# 25LC020A.net
KiCad netlist of a schematic drawn in EAGLE
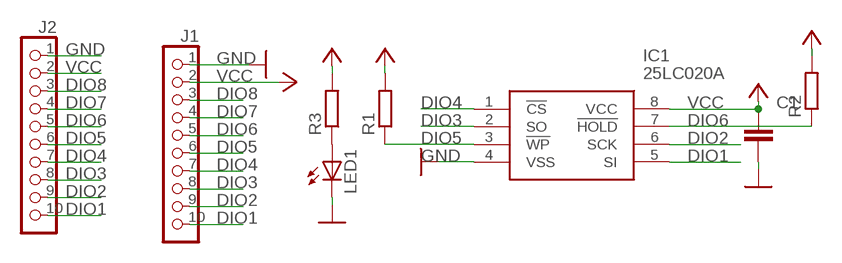
[diagram p0: schematic, sheet 1]

(export (version "E")
  (design (tool "Eeschema 10.0.6"))
  (components
    (comp (ref "C1")
      (value "CAPACITOR_NPOL-0603")
      (footprint "eagle-import:C603")
      (libsource (lib "eagle-import") (part "CAPACITOR_NPOL-0603"))
    )
    (comp (ref "IC1")
      (value "25LC020A")
      (footprint "eagle-import:SOIC127P600X175-8N")
      (fields (field (name "MANUFACTURER_PART_NUMBER") "25LC020A-I/SN"))
      (libsource (lib "eagle-import") (part "25LC020A-I_SN"))
    )
    (comp (ref "J1")
      (value "CON_HEADER_1X10-RIGHT_ANGLED_PTH")
      (footprint "eagle-import:M1X10_FEMALE_RIGHT_ANGLED_PTH")
      (libsource (lib "eagle-import") (part "CON_HEADER_1X10-RIGHT_ANGLED_PTH"))
    )
    (comp (ref "J2")
      (value "CON_HEADER_1X10-PTH")
      (footprint "eagle-import:M1X10")
      (libsource (lib "eagle-import") (part "CON_HEADER_1X10-PTH"))
    )
    (comp (ref "LED1")
      (value "LED-0805")
      (footprint "eagle-import:LED-805")
      (libsource (lib "eagle-import") (part "LED-0805"))
    )
    (comp (ref "R1")
      (value "RESISTOR-0603")
      (footprint "eagle-import:R603")
      (libsource (lib "eagle-import") (part "RESISTOR-0603"))
    )
    (comp (ref "R2")
      (value "RESISTOR-0603")
      (footprint "eagle-import:R603")
      (libsource (lib "eagle-import") (part "RESISTOR-0603"))
    )
    (comp (ref "R3")
      (value "RESISTOR-0603")
      (footprint "eagle-import:R603")
      (libsource (lib "eagle-import") (part "RESISTOR-0603"))
    )
  )
  (nets
    (net (code "1") (name "/DIO1") (class "Default")
      (node (ref "IC1") (pin "5") (pinfunction "SI_5") (pintype "bidirectional"))
      (node (ref "J1") (pin "10") (pinfunction "10_10") (pintype "passive"))
      (node (ref "J2") (pin "10") (pinfunction "10_10") (pintype "passive"))
    )
    (net (code "2") (name "/DIO2") (class "Default")
      (node (ref "IC1") (pin "6") (pinfunction "SCK_6") (pintype "bidirectional"))
      (node (ref "J1") (pin "9") (pinfunction "9_9") (pintype "passive"))
      (node (ref "J2") (pin "9") (pinfunction "9_9") (pintype "passive"))
    )
    (net (code "3") (name "/DIO3") (class "Default")
      (node (ref "IC1") (pin "2") (pinfunction "SO_2") (pintype "bidirectional"))
      (node (ref "J1") (pin "8") (pinfunction "8_8") (pintype "passive"))
      (node (ref "J2") (pin "8") (pinfunction "8_8") (pintype "passive"))
    )
    (net (code "4") (name "/DIO4") (class "Default")
      (node (ref "IC1") (pin "1") (pinfunction "~{CS}_1") (pintype "input"))
      (node (ref "J1") (pin "7") (pinfunction "7_7") (pintype "passive"))
      (node (ref "J2") (pin "7") (pinfunction "7_7") (pintype "passive"))
    )
    (net (code "5") (name "/DIO5") (class "Default")
      (node (ref "IC1") (pin "3") (pinfunction "~{WP}_3") (pintype "bidirectional"))
      (node (ref "J1") (pin "6") (pinfunction "6_6") (pintype "passive"))
      (node (ref "J2") (pin "6") (pinfunction "6_6") (pintype "passive"))
      (node (ref "R1") (pin "1") (pinfunction "1_1") (pintype "passive"))
    )
    (net (code "6") (name "/DIO6") (class "Default")
      (node (ref "IC1") (pin "7") (pinfunction "~{HOLD}_7") (pintype "bidirectional"))
      (node (ref "J1") (pin "5") (pinfunction "5_5") (pintype "passive"))
      (node (ref "J2") (pin "5") (pinfunction "5_5") (pintype "passive"))
      (node (ref "R2") (pin "1") (pinfunction "1_1") (pintype "passive"))
    )
    (net (code "7") (name "/DIO7") (class "Default")
      (node (ref "J1") (pin "4") (pinfunction "4_4") (pintype "passive"))
      (node (ref "J2") (pin "4") (pinfunction "4_4") (pintype "passive"))
    )
    (net (code "8") (name "/DIO8") (class "Default")
      (node (ref "J1") (pin "3") (pinfunction "3_3") (pintype "passive"))
      (node (ref "J2") (pin "3") (pinfunction "3_3") (pintype "passive"))
    )
    (net (code "9") (name "GND") (class "Default")
      (node (ref "C1") (pin "2") (pinfunction "2_2") (pintype "passive"))
      (node (ref "IC1") (pin "4") (pinfunction "VSS_4") (pintype "power_in"))
      (node (ref "J1") (pin "1") (pinfunction "1_1") (pintype "passive"))
      (node (ref "J2") (pin "1") (pinfunction "1_1") (pintype "passive"))
      (node (ref "LED1") (pin "C") (pinfunction "C_C") (pintype "passive"))
    )
    (net (code "10") (name "Net-(LED1-PadA)") (class "Default")
      (node (ref "LED1") (pin "A") (pinfunction "A_A") (pintype "passive"))
      (node (ref "R3") (pin "1") (pinfunction "1_1") (pintype "passive"))
    )
    (net (code "11") (name "VCC") (class "Default")
      (node (ref "C1") (pin "1") (pinfunction "1_1") (pintype "passive"))
      (node (ref "IC1") (pin "8") (pinfunction "VCC_8") (pintype "power_in"))
      (node (ref "J1") (pin "2") (pinfunction "2_2") (pintype "passive"))
      (node (ref "J2") (pin "2") (pinfunction "2_2") (pintype "passive"))
      (node (ref "R1") (pin "2") (pinfunction "2_2") (pintype "passive"))
      (node (ref "R2") (pin "2") (pinfunction "2_2") (pintype "passive"))
      (node (ref "R3") (pin "2") (pinfunction "2_2") (pintype "passive"))
    )
  )
)
